# ADC-Bessel-LPF.net
KiCad netlist of a schematic drawn in Altium Designer
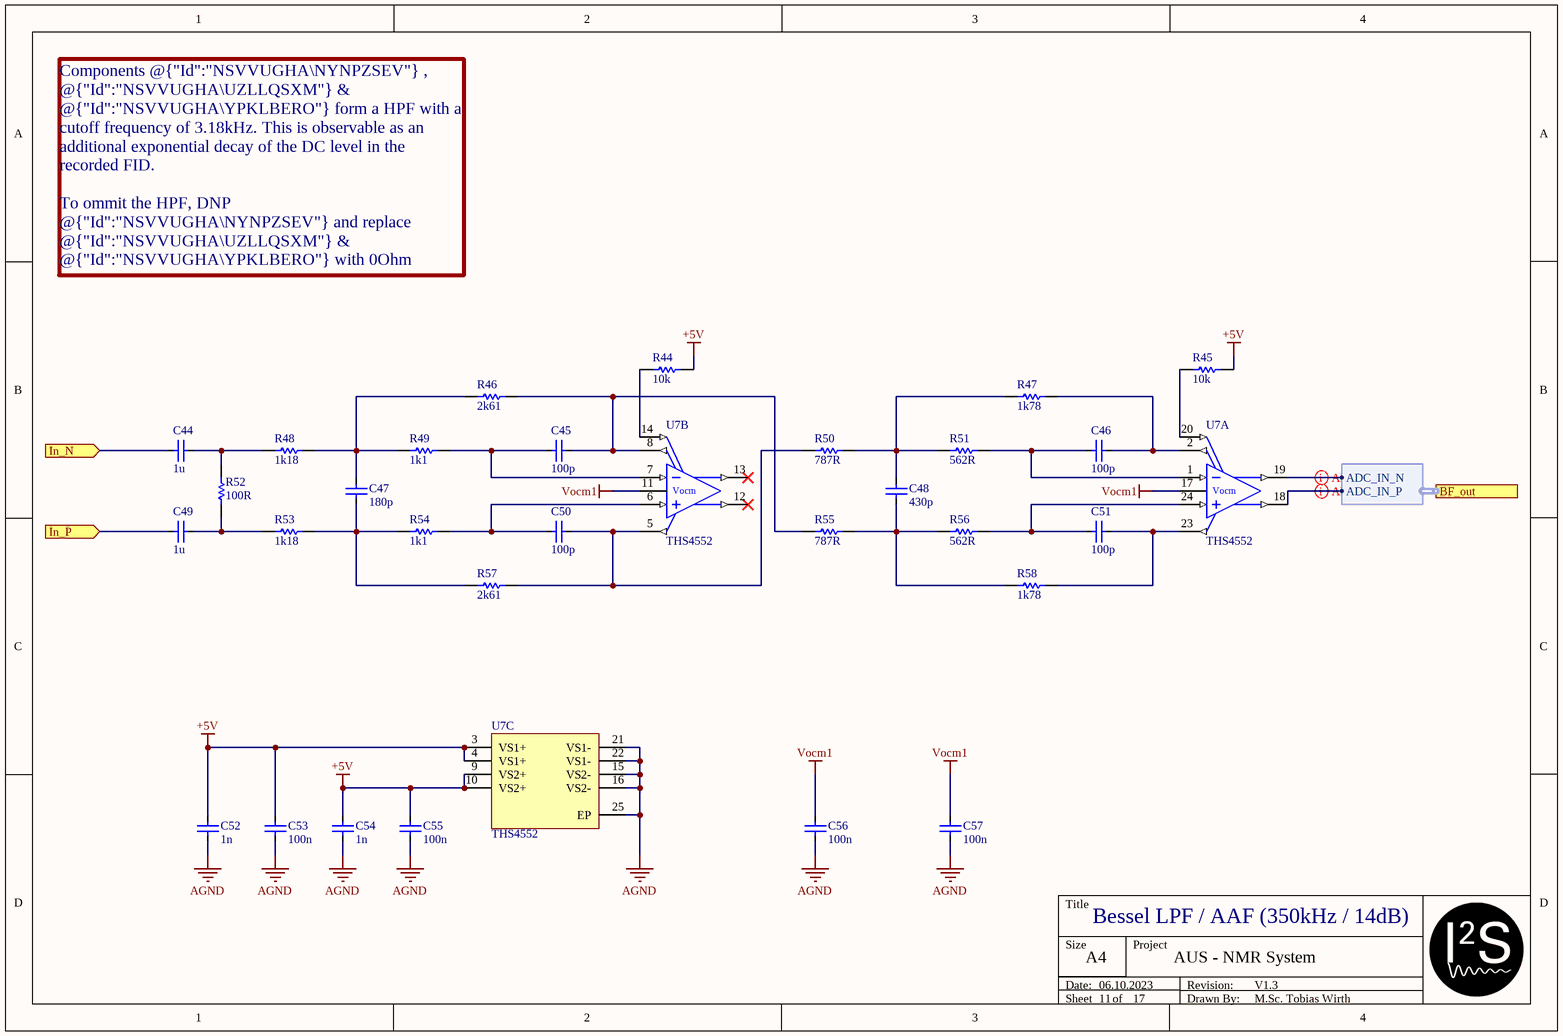
[diagram p0: ADC-Bessel-LPF.SchDoc]

(export (version "E")
  (design (tool "Eeschema 10.0.6"))
  (components
    (comp (ref "C44") (value "1u") (footprint "CAP_0402") (libsource (lib "IIS-Lib_TW") (part "Cap")))
    (comp (ref "C45") (value "100p") (footprint "CAP_0402") (libsource (lib "IIS-Lib_TW") (part "Cap")))
    (comp (ref "C46") (value "100p") (footprint "CAP_0402") (libsource (lib "IIS-Lib_TW") (part "Cap")))
    (comp (ref "C47") (value "180p") (footprint "CAP_0402") (libsource (lib "IIS-Lib_TW") (part "Cap")))
    (comp (ref "C48") (value "430p") (footprint "CAP_0402") (libsource (lib "IIS-Lib_TW") (part "Cap")))
    (comp (ref "C49") (value "1u") (footprint "CAP_0402") (libsource (lib "IIS-Lib_TW") (part "Cap")))
    (comp (ref "C50") (value "100p") (footprint "CAP_0402") (libsource (lib "IIS-Lib_TW") (part "Cap")))
    (comp (ref "C51") (value "100p") (footprint "CAP_0402") (libsource (lib "IIS-Lib_TW") (part "Cap")))
    (comp (ref "C52") (value "1n") (footprint "CAP_0402") (libsource (lib "IIS-Lib_TW") (part "Cap")))
    (comp (ref "C53") (value "100n") (footprint "CAP_0402") (libsource (lib "IIS-Lib_TW") (part "Cap")))
    (comp (ref "C54") (value "1n") (footprint "CAP_0402") (libsource (lib "IIS-Lib_TW") (part "Cap")))
    (comp (ref "C55") (value "100n") (footprint "CAP_0402") (libsource (lib "IIS-Lib_TW") (part "Cap")))
    (comp (ref "C56") (value "100n") (footprint "CAP_0402") (libsource (lib "IIS-Lib_TW") (part "Cap")))
    (comp (ref "C57") (value "100n") (footprint "CAP_0402") (libsource (lib "IIS-Lib_TW") (part "Cap")))
    (comp (ref "R44") (value "10k") (footprint "RES_0402") (libsource (lib "IIS-Lib_TW") (part "Res")))
    (comp (ref "R45") (value "10k") (footprint "RES_0402") (libsource (lib "IIS-Lib_TW") (part "Res")))
    (comp (ref "R46") (value "2k61") (footprint "RES_0402") (libsource (lib "IIS-Lib_TW") (part "Res")))
    (comp (ref "R47") (value "1k78") (footprint "RES_0402") (libsource (lib "IIS-Lib_TW") (part "Res")))
    (comp (ref "R48") (value "1k18") (footprint "RES_0402") (libsource (lib "IIS-Lib_TW") (part "Res")))
    (comp (ref "R49") (value "1k1") (footprint "RES_0402") (libsource (lib "IIS-Lib_TW") (part "Res")))
    (comp (ref "R50") (value "787R") (footprint "RES_0402") (libsource (lib "IIS-Lib_TW") (part "Res")))
    (comp (ref "R51") (value "562R") (footprint "RES_0402") (libsource (lib "IIS-Lib_TW") (part "Res")))
    (comp (ref "R52") (value "100R") (footprint "RES_0402") (libsource (lib "IIS-Lib_TW") (part "Res")))
    (comp (ref "R53") (value "1k18") (footprint "RES_0402") (libsource (lib "IIS-Lib_TW") (part "Res")))
    (comp (ref "R54") (value "1k1") (footprint "RES_0402") (libsource (lib "IIS-Lib_TW") (part "Res")))
    (comp (ref "R55") (value "787R") (footprint "RES_0402") (libsource (lib "IIS-Lib_TW") (part "Res")))
    (comp (ref "R56") (value "562R") (footprint "RES_0402") (libsource (lib "IIS-Lib_TW") (part "Res")))
    (comp (ref "R57") (value "2k61") (footprint "RES_0402") (libsource (lib "IIS-Lib_TW") (part "Res")))
    (comp (ref "R58") (value "1k78") (footprint "RES_0402") (libsource (lib "IIS-Lib_TW") (part "Res")))
    (comp (ref "U7")
      (value "THS4552")
      (footprint "IIS-Lib_TW:QFN-24Pin_TP")
      (description "Dual-Channel, Low-Noise, Precision, 150-MHz, Fully Differential Amplifier")
      (fields
        (field (name "MOUSER2 PART NUMBER") "595-THS4552IRTWT")
        (field (name "MANUFACTURER_PART_NUMBER") "THS4552IRTWT")
      )
      (libsource (lib "IIS-Lib_TW") (part "THS4552"))
    )
  )
  (nets
    (net (code "2") (name "+5V") (class "Default")
      (node (ref "C52") (pin "1") (pinfunction "1_1") (pintype "passive"))
      (node (ref "C53") (pin "1") (pinfunction "1_1") (pintype "passive"))
      (node (ref "C54") (pin "1") (pinfunction "1_1") (pintype "passive"))
      (node (ref "C55") (pin "1") (pinfunction "1_1") (pintype "passive"))
      (node (ref "R44") (pin "2") (pinfunction "2_2") (pintype "passive"))
      (node (ref "R45") (pin "2") (pinfunction "2_2") (pintype "passive"))
      (node (ref "U7") (pin "10") (pinfunction "VS2+_10") (pintype "power_in"))
      (node (ref "U7") (pin "3") (pinfunction "VS1+_3") (pintype "power_in"))
      (node (ref "U7") (pin "4") (pinfunction "VS1+_4") (pintype "power_in"))
      (node (ref "U7") (pin "9") (pinfunction "VS2+_9") (pintype "power_in"))
    )
    (net (code "3") (name "/ADC_IN_N") (class "Default")
      (node (ref "U7") (pin "19") (pinfunction "OUT1-_19") (pintype "output"))
    )
    (net (code "4") (name "/ADC_IN_P") (class "Default")
      (node (ref "U7") (pin "18") (pinfunction "OUT1+_18") (pintype "output"))
    )
    (net (code "5") (name "/In_N") (class "Default")
      (node (ref "C44") (pin "1") (pinfunction "1_1") (pintype "passive"))
    )
    (net (code "6") (name "/In_P") (class "Default")
      (node (ref "C49") (pin "1") (pinfunction "1_1") (pintype "passive"))
    )
    (net (code "8") (name "AGND") (class "Default")
      (node (ref "C52") (pin "2") (pinfunction "2_2") (pintype "passive"))
      (node (ref "C53") (pin "2") (pinfunction "2_2") (pintype "passive"))
      (node (ref "C54") (pin "2") (pinfunction "2_2") (pintype "passive"))
      (node (ref "C55") (pin "2") (pinfunction "2_2") (pintype "passive"))
      (node (ref "C56") (pin "2") (pinfunction "2_2") (pintype "passive"))
      (node (ref "C57") (pin "2") (pinfunction "2_2") (pintype "passive"))
      (node (ref "U7") (pin "15") (pinfunction "VS2-_15") (pintype "power_in"))
      (node (ref "U7") (pin "16") (pinfunction "VS2-_16") (pintype "power_in"))
      (node (ref "U7") (pin "21") (pinfunction "VS1-_21") (pintype "power_in"))
      (node (ref "U7") (pin "22") (pinfunction "VS1-_22") (pintype "power_in"))
      (node (ref "U7") (pin "25") (pinfunction "EP_25") (pintype "power_in"))
    )
    (net (code "9") (name "Net-(C44-Pad2)") (class "Default")
      (node (ref "C44") (pin "2") (pinfunction "2_2") (pintype "passive"))
      (node (ref "R48") (pin "1") (pinfunction "1_1") (pintype "passive"))
      (node (ref "R52") (pin "2") (pinfunction "2_2") (pintype "passive"))
    )
    (net (code "10") (name "Net-(C47-Pad1)") (class "Default")
      (node (ref "C47") (pin "1") (pinfunction "1_1") (pintype "passive"))
      (node (ref "R46") (pin "1") (pinfunction "1_1") (pintype "passive"))
      (node (ref "R48") (pin "2") (pinfunction "2_2") (pintype "passive"))
      (node (ref "R49") (pin "1") (pinfunction "1_1") (pintype "passive"))
    )
    (net (code "11") (name "Net-(C47-Pad2)") (class "Default")
      (node (ref "C47") (pin "2") (pinfunction "2_2") (pintype "passive"))
      (node (ref "R53") (pin "2") (pinfunction "2_2") (pintype "passive"))
      (node (ref "R54") (pin "1") (pinfunction "1_1") (pintype "passive"))
      (node (ref "R57") (pin "1") (pinfunction "1_1") (pintype "passive"))
    )
    (net (code "12") (name "Net-(C48-Pad1)") (class "Default")
      (node (ref "C48") (pin "1") (pinfunction "1_1") (pintype "passive"))
      (node (ref "R47") (pin "1") (pinfunction "1_1") (pintype "passive"))
      (node (ref "R50") (pin "2") (pinfunction "2_2") (pintype "passive"))
      (node (ref "R51") (pin "1") (pinfunction "1_1") (pintype "passive"))
    )
    (net (code "13") (name "Net-(C48-Pad2)") (class "Default")
      (node (ref "C48") (pin "2") (pinfunction "2_2") (pintype "passive"))
      (node (ref "R55") (pin "2") (pinfunction "2_2") (pintype "passive"))
      (node (ref "R56") (pin "1") (pinfunction "1_1") (pintype "passive"))
      (node (ref "R58") (pin "1") (pinfunction "1_1") (pintype "passive"))
    )
    (net (code "14") (name "Net-(C49-Pad2)") (class "Default")
      (node (ref "C49") (pin "2") (pinfunction "2_2") (pintype "passive"))
      (node (ref "R52") (pin "1") (pinfunction "1_1") (pintype "passive"))
      (node (ref "R53") (pin "1") (pinfunction "1_1") (pintype "passive"))
    )
    (net (code "15") (name "Net-(U7A-FB1+)") (class "Default")
      (node (ref "C46") (pin "1") (pinfunction "1_1") (pintype "passive"))
      (node (ref "R47") (pin "2") (pinfunction "2_2") (pintype "passive"))
      (node (ref "U7") (pin "2") (pinfunction "FB1+_2") (pintype "output"))
    )
    (net (code "16") (name "Net-(U7A-FB1-)") (class "Default")
      (node (ref "C51") (pin "1") (pinfunction "1_1") (pintype "passive"))
      (node (ref "R58") (pin "2") (pinfunction "2_2") (pintype "passive"))
      (node (ref "U7") (pin "23") (pinfunction "FB1-_23") (pintype "output"))
    )
    (net (code "17") (name "Net-(U7A-IN1+)") (class "Default")
      (node (ref "C51") (pin "2") (pinfunction "2_2") (pintype "passive"))
      (node (ref "R56") (pin "2") (pinfunction "2_2") (pintype "passive"))
      (node (ref "U7") (pin "24") (pinfunction "IN1+_24") (pintype "input"))
    )
    (net (code "18") (name "Net-(U7A-IN1-)") (class "Default")
      (node (ref "C46") (pin "2") (pinfunction "2_2") (pintype "passive"))
      (node (ref "R51") (pin "2") (pinfunction "2_2") (pintype "passive"))
      (node (ref "U7") (pin "1") (pinfunction "IN1-_1") (pintype "input"))
    )
    (net (code "19") (name "Net-(U7A-~{PD1})") (class "Default")
      (node (ref "R45") (pin "1") (pinfunction "1_1") (pintype "passive"))
      (node (ref "U7") (pin "20") (pinfunction "~{PD1}_20") (pintype "input"))
    )
    (net (code "20") (name "Net-(U7B-FB2+)") (class "Default")
      (node (ref "C45") (pin "1") (pinfunction "1_1") (pintype "passive"))
      (node (ref "R46") (pin "2") (pinfunction "2_2") (pintype "passive"))
      (node (ref "R55") (pin "1") (pinfunction "1_1") (pintype "passive"))
      (node (ref "U7") (pin "8") (pinfunction "FB2+_8") (pintype "output"))
    )
    (net (code "21") (name "Net-(U7B-FB2-)") (class "Default")
      (node (ref "C50") (pin "1") (pinfunction "1_1") (pintype "passive"))
      (node (ref "R50") (pin "1") (pinfunction "1_1") (pintype "passive"))
      (node (ref "R57") (pin "2") (pinfunction "2_2") (pintype "passive"))
      (node (ref "U7") (pin "5") (pinfunction "FB2-_5") (pintype "output"))
    )
    (net (code "22") (name "Net-(U7B-IN2+)") (class "Default")
      (node (ref "C50") (pin "2") (pinfunction "2_2") (pintype "passive"))
      (node (ref "R54") (pin "2") (pinfunction "2_2") (pintype "passive"))
      (node (ref "U7") (pin "6") (pinfunction "IN2+_6") (pintype "input"))
    )
    (net (code "23") (name "Net-(U7B-IN2-)") (class "Default")
      (node (ref "C45") (pin "2") (pinfunction "2_2") (pintype "passive"))
      (node (ref "R49") (pin "2") (pinfunction "2_2") (pintype "passive"))
      (node (ref "U7") (pin "7") (pinfunction "IN2-_7") (pintype "input"))
    )
    (net (code "24") (name "Net-(U7B-~{PD2})") (class "Default")
      (node (ref "R44") (pin "1") (pinfunction "1_1") (pintype "passive"))
      (node (ref "U7") (pin "14") (pinfunction "~{PD2}_14") (pintype "input"))
    )
    (net (code "25") (name "Vocm1") (class "Default")
      (node (ref "C56") (pin "1") (pinfunction "1_1") (pintype "passive"))
      (node (ref "C57") (pin "1") (pinfunction "1_1") (pintype "passive"))
      (node (ref "U7") (pin "11") (pinfunction "VOCM2_11") (pintype "power_in"))
      (node (ref "U7") (pin "17") (pinfunction "VOCM1_17") (pintype "power_in"))
    )
    (net (code "26") (name "unconnected-(U7B-OUT2+-Pad12)") (class "Default")
      (node (ref "U7") (pin "12") (pinfunction "OUT2+_12") (pintype "output+no_connect"))
    )
    (net (code "27") (name "unconnected-(U7B-OUT2--Pad13)") (class "Default")
      (node (ref "U7") (pin "13") (pinfunction "OUT2-_13") (pintype "output+no_connect"))
    )
  )
)
